# Nonaddressable_Controller.net
KiCad netlist of a schematic drawn in EAGLE
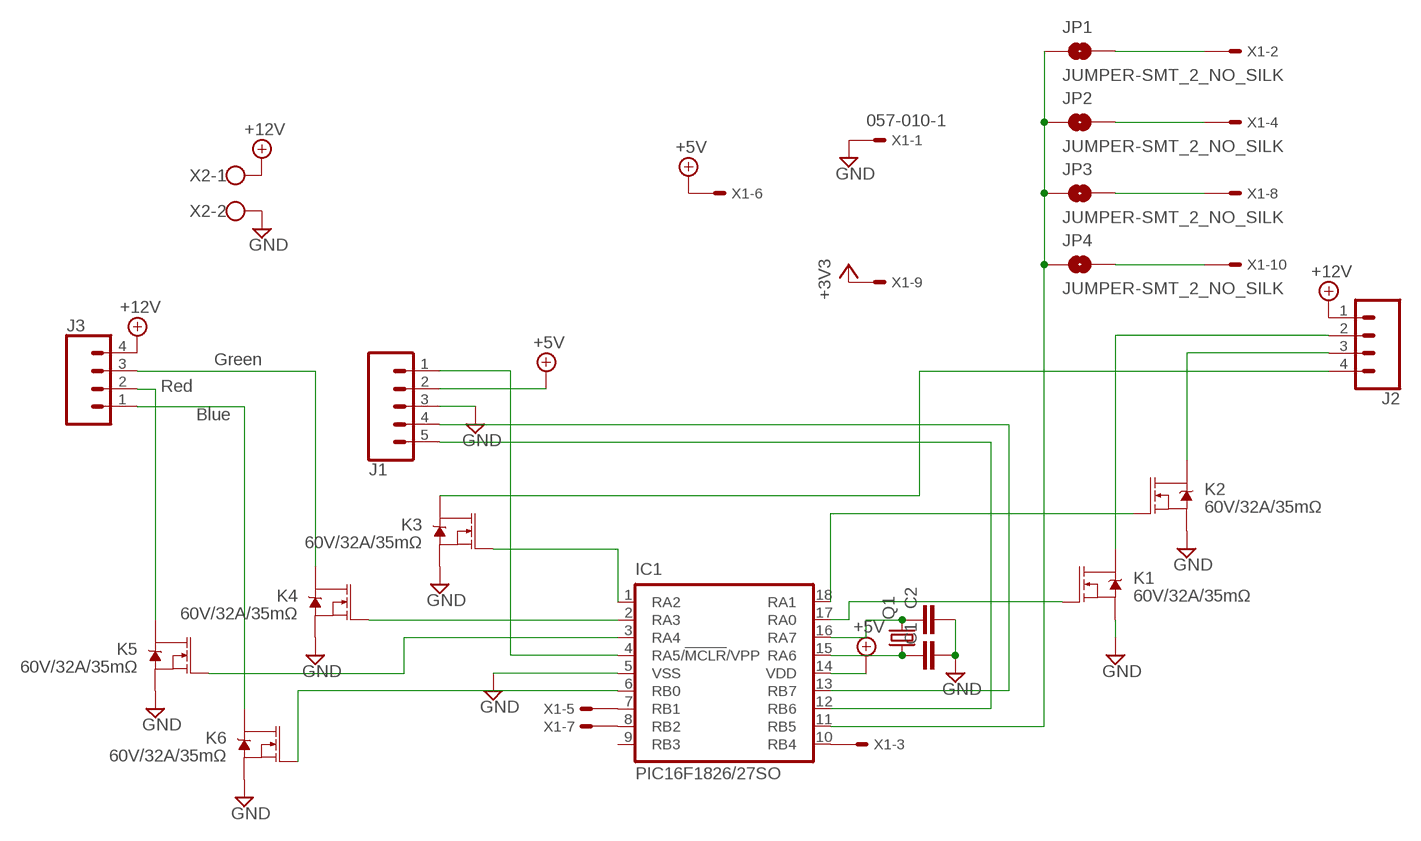
[diagram p0: schematic, sheet 1]

(export (version "E")
  (design (tool "Eeschema 10.0.6"))
  (components
    (comp (ref "C1")
      (value "C-EUC1206")
      (footprint "eagle-import:C1206")
      (libsource (lib "eagle-import") (part "C-EUC1206"))
    )
    (comp (ref "C2")
      (value "C-EUC1206")
      (footprint "eagle-import:C1206")
      (libsource (lib "eagle-import") (part "C-EUC1206"))
    )
    (comp (ref "IC1")
      (value "PIC16F1826/27SO")
      (footprint "eagle-import:SO-18W")
      (libsource (lib "eagle-import") (part "PIC16F1826/27SO"))
    )
    (comp (ref "J1")
      (value "CONN_05")
      (footprint "eagle-import:1X05")
      (libsource (lib "eagle-import") (part "CONN_05"))
    )
    (comp (ref "J2")
      (value "CONN_04")
      (footprint "eagle-import:1X04")
      (libsource (lib "eagle-import") (part "CONN_04"))
    )
    (comp (ref "J3")
      (value "CONN_04")
      (footprint "eagle-import:1X04")
      (libsource (lib "eagle-import") (part "CONN_04"))
    )
    (comp (ref "JP1")
      (value "JUMPER-SMT_2_NO_SILK")
      (footprint "eagle-import:SMT-JUMPER_2_NO_SILK")
      (libsource (lib "eagle-import") (part "JUMPER-SMT_2_NO_SILK"))
    )
    (comp (ref "JP2")
      (value "JUMPER-SMT_2_NO_SILK")
      (footprint "eagle-import:SMT-JUMPER_2_NO_SILK")
      (libsource (lib "eagle-import") (part "JUMPER-SMT_2_NO_SILK"))
    )
    (comp (ref "JP3")
      (value "JUMPER-SMT_2_NO_SILK")
      (footprint "eagle-import:SMT-JUMPER_2_NO_SILK")
      (libsource (lib "eagle-import") (part "JUMPER-SMT_2_NO_SILK"))
    )
    (comp (ref "JP4")
      (value "JUMPER-SMT_2_NO_SILK")
      (footprint "eagle-import:SMT-JUMPER_2_NO_SILK")
      (libsource (lib "eagle-import") (part "JUMPER-SMT_2_NO_SILK"))
    )
    (comp (ref "K1")
      (value "60V/32A/35mΩ")
      (footprint "eagle-import:TO220V")
      (libsource (lib "eagle-import") (part "MOSFET-NCH-FQP30N06L"))
    )
    (comp (ref "K2")
      (value "60V/32A/35mΩ")
      (footprint "eagle-import:TO220V")
      (libsource (lib "eagle-import") (part "MOSFET-NCH-FQP30N06L"))
    )
    (comp (ref "K3")
      (value "60V/32A/35mΩ")
      (footprint "eagle-import:TO220V")
      (libsource (lib "eagle-import") (part "MOSFET-NCH-FQP30N06L"))
    )
    (comp (ref "K4")
      (value "60V/32A/35mΩ")
      (footprint "eagle-import:TO220V")
      (libsource (lib "eagle-import") (part "MOSFET-NCH-FQP30N06L"))
    )
    (comp (ref "K5")
      (value "60V/32A/35mΩ")
      (footprint "eagle-import:TO220V")
      (libsource (lib "eagle-import") (part "MOSFET-NCH-FQP30N06L"))
    )
    (comp (ref "K6")
      (value "60V/32A/35mΩ")
      (footprint "eagle-import:TO220V")
      (libsource (lib "eagle-import") (part "MOSFET-NCH-FQP30N06L"))
    )
    (comp (ref "Q1")
      (value "CRYSTALHC49S")
      (footprint "eagle-import:HC49_S")
      (libsource (lib "eagle-import") (part "CRYSTALHC49S"))
    )
    (comp (ref "X1")
      (value "057-010-1")
      (footprint "eagle-import:057-010-1")
      (libsource (lib "eagle-import") (part "057-010-1"))
    )
    (comp (ref "X2")
      (value "W237-102")
      (footprint "eagle-import:W237-102")
      (fields (field (name "MPN") "237-102"))
      (libsource (lib "eagle-import") (part "W237-102"))
    )
  )
  (nets
    (net (code "1") (name "+3V3") (class "Default")
      (node (ref "X1") (pin "9") (pinfunction "S_9") (pintype "passive"))
    )
    (net (code "2") (name "+5V") (class "Default")
      (node (ref "IC1") (pin "14") (pinfunction "VDD_14") (pintype "power_in"))
      (node (ref "J1") (pin "2") (pinfunction "2_2") (pintype "passive"))
      (node (ref "X1") (pin "6") (pinfunction "S_6") (pintype "passive"))
    )
    (net (code "3") (name "+12V") (class "Default")
      (node (ref "J2") (pin "1") (pinfunction "1_1") (pintype "passive"))
      (node (ref "J3") (pin "4") (pinfunction "4_4") (pintype "passive"))
      (node (ref "X2") (pin "1") (pinfunction "KL_1") (pintype "passive"))
    )
    (net (code "4") (name "GND") (class "Default")
      (node (ref "C1") (pin "2") (pinfunction "2_2") (pintype "passive"))
      (node (ref "C2") (pin "2") (pinfunction "2_2") (pintype "passive"))
      (node (ref "IC1") (pin "5") (pinfunction "VSS_5") (pintype "power_in"))
      (node (ref "J1") (pin "3") (pinfunction "3_3") (pintype "passive"))
      (node (ref "K1") (pin "3") (pinfunction "S_3") (pintype "bidirectional"))
      (node (ref "K2") (pin "3") (pinfunction "S_3") (pintype "bidirectional"))
      (node (ref "K3") (pin "3") (pinfunction "S_3") (pintype "bidirectional"))
      (node (ref "K4") (pin "3") (pinfunction "S_3") (pintype "bidirectional"))
      (node (ref "K5") (pin "3") (pinfunction "S_3") (pintype "bidirectional"))
      (node (ref "K6") (pin "3") (pinfunction "S_3") (pintype "bidirectional"))
      (node (ref "X1") (pin "1") (pinfunction "S_1") (pintype "passive"))
      (node (ref "X2") (pin "2") (pinfunction "KL_2") (pintype "passive"))
    )
    (net (code "5") (name "Net-(IC1-RA0)") (class "Default")
      (node (ref "IC1") (pin "17") (pinfunction "RA0_17") (pintype "bidirectional"))
      (node (ref "K1") (pin "1") (pinfunction "G_1") (pintype "bidirectional"))
    )
    (net (code "6") (name "Net-(IC1-RA1)") (class "Default")
      (node (ref "IC1") (pin "18") (pinfunction "RA1_18") (pintype "bidirectional"))
      (node (ref "K2") (pin "1") (pinfunction "G_1") (pintype "bidirectional"))
    )
    (net (code "7") (name "Net-(IC1-RA2)") (class "Default")
      (node (ref "IC1") (pin "1") (pinfunction "RA2_1") (pintype "bidirectional"))
      (node (ref "K3") (pin "1") (pinfunction "G_1") (pintype "bidirectional"))
    )
    (net (code "8") (name "Net-(IC1-RA3)") (class "Default")
      (node (ref "IC1") (pin "2") (pinfunction "RA3_2") (pintype "bidirectional"))
      (node (ref "K4") (pin "1") (pinfunction "G_1") (pintype "bidirectional"))
    )
    (net (code "9") (name "Net-(IC1-RA4)") (class "Default")
      (node (ref "IC1") (pin "3") (pinfunction "RA4_3") (pintype "bidirectional"))
      (node (ref "K5") (pin "1") (pinfunction "G_1") (pintype "bidirectional"))
    )
    (net (code "10") (name "Net-(IC1-RA5{slash}~{MCLR}{slash}VPP)") (class "Default")
      (node (ref "IC1") (pin "4") (pinfunction "RA5/~{MCLR}/VPP_4") (pintype "bidirectional"))
      (node (ref "J1") (pin "1") (pinfunction "1_1") (pintype "passive"))
    )
    (net (code "11") (name "Net-(IC1-RA6)") (class "Default")
      (node (ref "C1") (pin "1") (pinfunction "1_1") (pintype "passive"))
      (node (ref "IC1") (pin "15") (pinfunction "RA6_15") (pintype "bidirectional"))
      (node (ref "Q1") (pin "1") (pinfunction "1_1") (pintype "passive"))
    )
    (net (code "12") (name "Net-(IC1-RA7)") (class "Default")
      (node (ref "C2") (pin "1") (pinfunction "1_1") (pintype "passive"))
      (node (ref "IC1") (pin "16") (pinfunction "RA7_16") (pintype "bidirectional"))
      (node (ref "Q1") (pin "2") (pinfunction "2_2") (pintype "passive"))
    )
    (net (code "13") (name "Net-(IC1-RB0)") (class "Default")
      (node (ref "IC1") (pin "6") (pinfunction "RB0_6") (pintype "bidirectional"))
      (node (ref "K6") (pin "1") (pinfunction "G_1") (pintype "bidirectional"))
    )
    (net (code "14") (name "Net-(IC1-RB1)") (class "Default")
      (node (ref "IC1") (pin "7") (pinfunction "RB1_7") (pintype "bidirectional"))
      (node (ref "X1") (pin "5") (pinfunction "S_5") (pintype "passive"))
    )
    (net (code "15") (name "Net-(IC1-RB2)") (class "Default")
      (node (ref "IC1") (pin "8") (pinfunction "RB2_8") (pintype "bidirectional"))
      (node (ref "X1") (pin "7") (pinfunction "S_7") (pintype "passive"))
    )
    (net (code "16") (name "Net-(IC1-RB4)") (class "Default")
      (node (ref "IC1") (pin "10") (pinfunction "RB4_10") (pintype "bidirectional"))
      (node (ref "X1") (pin "3") (pinfunction "S_3") (pintype "passive"))
    )
    (net (code "17") (name "Net-(IC1-RB5)") (class "Default")
      (node (ref "IC1") (pin "11") (pinfunction "RB5_11") (pintype "bidirectional"))
      (node (ref "JP1") (pin "1") (pinfunction "1_1") (pintype "passive"))
      (node (ref "JP2") (pin "1") (pinfunction "1_1") (pintype "passive"))
      (node (ref "JP3") (pin "1") (pinfunction "1_1") (pintype "passive"))
      (node (ref "JP4") (pin "1") (pinfunction "1_1") (pintype "passive"))
    )
    (net (code "18") (name "Net-(IC1-RB6)") (class "Default")
      (node (ref "IC1") (pin "12") (pinfunction "RB6_12") (pintype "bidirectional"))
      (node (ref "J1") (pin "5") (pinfunction "5_5") (pintype "passive"))
    )
    (net (code "19") (name "Net-(IC1-RB7)") (class "Default")
      (node (ref "IC1") (pin "13") (pinfunction "RB7_13") (pintype "bidirectional"))
      (node (ref "J1") (pin "4") (pinfunction "4_4") (pintype "passive"))
    )
    (net (code "20") (name "Net-(K1-D)") (class "Default")
      (node (ref "J2") (pin "2") (pinfunction "2_2") (pintype "passive"))
      (node (ref "K1") (pin "2") (pinfunction "D_2") (pintype "bidirectional"))
    )
    (net (code "21") (name "Net-(K2-D)") (class "Default")
      (node (ref "J2") (pin "3") (pinfunction "3_3") (pintype "passive"))
      (node (ref "K2") (pin "2") (pinfunction "D_2") (pintype "bidirectional"))
    )
    (net (code "22") (name "Net-(K3-D)") (class "Default")
      (node (ref "J2") (pin "4") (pinfunction "4_4") (pintype "passive"))
      (node (ref "K3") (pin "2") (pinfunction "D_2") (pintype "bidirectional"))
    )
    (net (code "23") (name "Net-(K4-D)") (class "Default")
      (node (ref "J3") (pin "3") (pinfunction "3_3") (pintype "passive"))
      (node (ref "K4") (pin "2") (pinfunction "D_2") (pintype "bidirectional"))
    )
    (net (code "24") (name "Net-(K5-D)") (class "Default")
      (node (ref "J3") (pin "2") (pinfunction "2_2") (pintype "passive"))
      (node (ref "K5") (pin "2") (pinfunction "D_2") (pintype "bidirectional"))
    )
    (net (code "25") (name "Net-(K6-D)") (class "Default")
      (node (ref "J3") (pin "1") (pinfunction "1_1") (pintype "passive"))
      (node (ref "K6") (pin "2") (pinfunction "D_2") (pintype "bidirectional"))
    )
    (net (code "26") (name "Net-(X1B-S)") (class "Default")
      (node (ref "JP4") (pin "2") (pinfunction "2_2") (pintype "passive"))
      (node (ref "X1") (pin "10") (pinfunction "S_10") (pintype "passive"))
    )
    (net (code "27") (name "Net-(X1C-S)") (class "Default")
      (node (ref "JP1") (pin "2") (pinfunction "2_2") (pintype "passive"))
      (node (ref "X1") (pin "2") (pinfunction "S_2") (pintype "passive"))
    )
    (net (code "28") (name "Net-(X1E-S)") (class "Default")
      (node (ref "JP2") (pin "2") (pinfunction "2_2") (pintype "passive"))
      (node (ref "X1") (pin "4") (pinfunction "S_4") (pintype "passive"))
    )
    (net (code "29") (name "Net-(X1I-S)") (class "Default")
      (node (ref "JP3") (pin "2") (pinfunction "2_2") (pintype "passive"))
      (node (ref "X1") (pin "8") (pinfunction "S_8") (pintype "passive"))
    )
    (net (code "30") (name "unconnected-(IC1-RB3-Pad9)") (class "Default")
      (node (ref "IC1") (pin "9") (pinfunction "RB3_9") (pintype "bidirectional"))
    )
  )
)
